# IOBoard.net
KiCad netlist of a schematic drawn in EAGLE
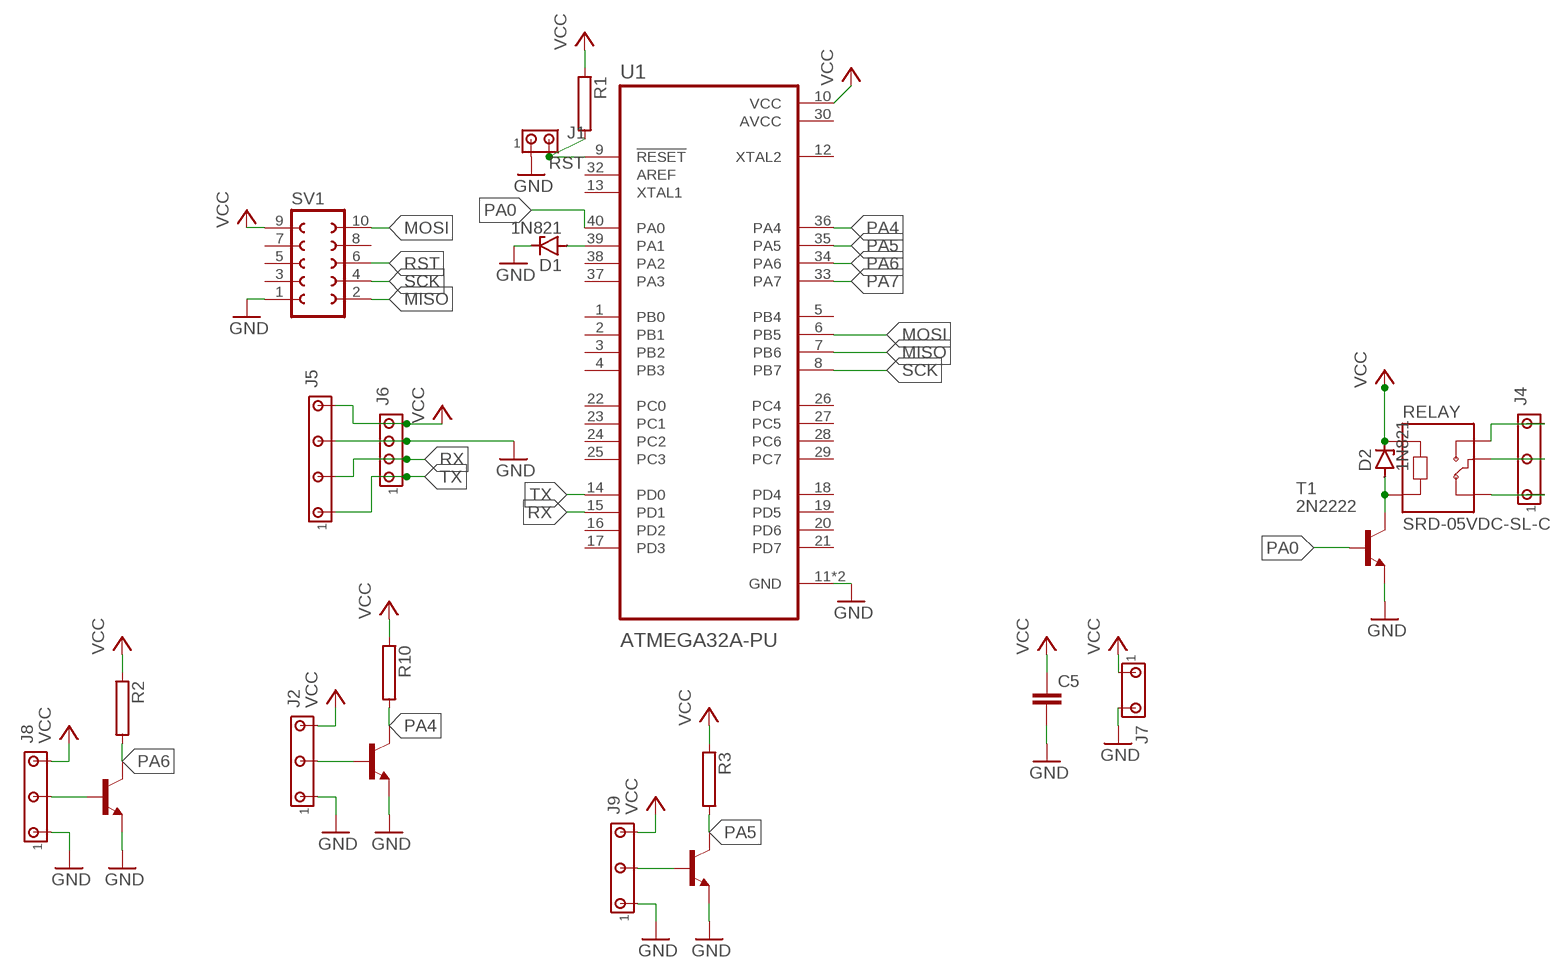
[diagram p0: schematic, sheet 1]

(export (version "E")
  (design (tool "Eeschema 10.0.6"))
  (components
    (comp (ref "C5")
      (value "C-EU025-024X044")
      (footprint "eagle-import:C025-024X044")
      (libsource (lib "eagle-import") (part "C-EU025-024X044"))
    )
    (comp (ref "D1")
      (value "1N821")
      (footprint "eagle-import:DO35Z10")
      (libsource (lib "eagle-import") (part "1N821"))
    )
    (comp (ref "D2")
      (value "1N821")
      (footprint "eagle-import:DO35Z10")
      (libsource (lib "eagle-import") (part "1N821"))
    )
    (comp (ref "J1")
      (value "MTA02-100")
      (footprint "eagle-import:10X02MTA")
      (libsource (lib "eagle-import") (part "MTA02-100"))
    )
    (comp (ref "J2")
      (value "MTA05-156_MYVSPACE1")
      (footprint "eagle-import:10X05MTA_MYV")
      (libsource (lib "eagle-import") (part "MTA05-156_MYVSPACE1"))
    )
    (comp (ref "J4")
      (value "MTA05-156_MYVSPACE1")
      (footprint "eagle-import:10X05MTA_MYV")
      (libsource (lib "eagle-import") (part "MTA05-156_MYVSPACE1"))
    )
    (comp (ref "J5")
      (value "MTA07-100_MYV")
      (footprint "eagle-import:10X07MTA_MYV")
      (libsource (lib "eagle-import") (part "MTA07-100_MYV"))
    )
    (comp (ref "J6")
      (value "MTA04-100")
      (footprint "eagle-import:10X04MTA")
      (libsource (lib "eagle-import") (part "MTA04-100"))
    )
    (comp (ref "J7")
      (value "MTA03-100_MYV")
      (footprint "eagle-import:10X03MTA_MYV")
      (libsource (lib "eagle-import") (part "MTA03-100_MYV"))
    )
    (comp (ref "J8")
      (value "MTA05-156_MYVSPACE1")
      (footprint "eagle-import:10X05MTA_MYV")
      (libsource (lib "eagle-import") (part "MTA05-156_MYVSPACE1"))
    )
    (comp (ref "J9")
      (value "MTA05-156_MYVSPACE1")
      (footprint "eagle-import:10X05MTA_MYV")
      (libsource (lib "eagle-import") (part "MTA05-156_MYVSPACE1"))
    )
    (comp (ref "R1")
      (value "RHPS58")
      (footprint "eagle-import:HPS58")
      (libsource (lib "eagle-import") (part "RHPS58"))
    )
    (comp (ref "R2")
      (value "RHPS58")
      (footprint "eagle-import:HPS58")
      (libsource (lib "eagle-import") (part "RHPS58"))
    )
    (comp (ref "R3")
      (value "RHPS58")
      (footprint "eagle-import:HPS58")
      (libsource (lib "eagle-import") (part "RHPS58"))
    )
    (comp (ref "R10")
      (value "RHPS58")
      (footprint "eagle-import:HPS58")
      (libsource (lib "eagle-import") (part "RHPS58"))
    )
    (comp (ref "RELAY")
      (value "SRD-05VDC-SL-C")
      (footprint "eagle-import:RELAY_SRD-05VDC-SL-C")
      (fields (field (name "MF") "Songle Relay"))
      (libsource (lib "eagle-import") (part "SRD-05VDC-SL-C"))
    )
    (comp (ref "SV1")
      (value "FE05-2_MYV")
      (footprint "eagle-import:FE05-2")
      (libsource (lib "eagle-import") (part "FE05-2_MYV"))
    )
    (comp (ref "T1")
      (value "2N2222")
      (footprint "eagle-import:TO18")
      (libsource (lib "eagle-import") (part "2N2222"))
    )
    (comp (ref "T2")
      (value "2N2222")
      (footprint "eagle-import:TO18")
      (libsource (lib "eagle-import") (part "2N2222"))
    )
    (comp (ref "T5")
      (value "2N2222")
      (footprint "eagle-import:TO18")
      (libsource (lib "eagle-import") (part "2N2222"))
    )
    (comp (ref "T6")
      (value "2N2222")
      (footprint "eagle-import:TO18")
      (libsource (lib "eagle-import") (part "2N2222"))
    )
    (comp (ref "U1")
      (value "ATMEGA32A-PU")
      (footprint "eagle-import:DIP1540W47P254L5320H635Q40B")
      (fields (field (name "MF") "Microchip Technology"))
      (libsource (lib "eagle-import") (part "ATMEGA32A-PU"))
    )
  )
  (nets
    (net (code "1") (name "/AVCC") (class "Default")
      (node (ref "U1") (pin "30") (pinfunction "AVCC_30") (pintype "power_in"))
    )
    (net (code "2") (name "GND") (class "Default")
      (node (ref "C5") (pin "2") (pinfunction "2_2") (pintype "passive"))
      (node (ref "D1") (pin "C") (pinfunction "C_C") (pintype "passive"))
      (node (ref "J1") (pin "1") (pinfunction "1_1") (pintype "passive"))
      (node (ref "J2") (pin "1") (pinfunction "1_1") (pintype "passive"))
      (node (ref "J5") (pin "5") (pinfunction "5_5") (pintype "passive"))
      (node (ref "J6") (pin "3") (pinfunction "3_3") (pintype "passive"))
      (node (ref "J7") (pin "3") (pinfunction "3_3") (pintype "passive"))
      (node (ref "J8") (pin "1") (pinfunction "1_1") (pintype "passive"))
      (node (ref "J9") (pin "1") (pinfunction "1_1") (pintype "passive"))
      (node (ref "SV1") (pin "1") (pinfunction "1_1") (pintype "passive"))
      (node (ref "T1") (pin "1") (pinfunction "E_1") (pintype "passive"))
      (node (ref "T2") (pin "1") (pinfunction "E_1") (pintype "passive"))
      (node (ref "T5") (pin "1") (pinfunction "E_1") (pintype "passive"))
      (node (ref "T6") (pin "1") (pinfunction "E_1") (pintype "passive"))
      (node (ref "U1") (pin "11") (pinfunction "GND_11") (pintype "power_in"))
      (node (ref "U1") (pin "31") (pinfunction "GND_31") (pintype "power_in"))
    )
    (net (code "3") (name "MISO") (class "Default")
      (node (ref "SV1") (pin "2") (pinfunction "2_2") (pintype "passive"))
      (node (ref "U1") (pin "7") (pinfunction "PB6_7") (pintype "bidirectional"))
    )
    (net (code "4") (name "MOSI") (class "Default")
      (node (ref "SV1") (pin "10") (pinfunction "10_10") (pintype "passive"))
      (node (ref "U1") (pin "6") (pinfunction "PB5_6") (pintype "bidirectional"))
    )
    (net (code "5") (name "Net-(J4-Pad1)") (class "Default")
      (node (ref "J4") (pin "1") (pinfunction "1_1") (pintype "passive"))
      (node (ref "RELAY") (pin "NC") (pinfunction "NC_NC") (pintype "passive"))
    )
    (net (code "6") (name "Net-(J4-Pad3)") (class "Default")
      (node (ref "J4") (pin "3") (pinfunction "3_3") (pintype "passive"))
      (node (ref "RELAY") (pin "COM") (pinfunction "COM_COM") (pintype "passive"))
    )
    (net (code "7") (name "Net-(J4-Pad5)") (class "Default")
      (node (ref "J4") (pin "5") (pinfunction "5_5") (pintype "passive"))
      (node (ref "RELAY") (pin "NO") (pinfunction "NO_NO") (pintype "passive"))
    )
    (net (code "8") (name "Net-(T1-C)") (class "Default")
      (node (ref "D2") (pin "A") (pinfunction "A_A") (pintype "passive"))
      (node (ref "RELAY") (pin "A2") (pinfunction "A2_A2") (pintype "passive"))
      (node (ref "T1") (pin "3") (pinfunction "C_3") (pintype "passive"))
    )
    (net (code "9") (name "Net-(T2-B)") (class "Default")
      (node (ref "J2") (pin "3") (pinfunction "3_3") (pintype "passive"))
      (node (ref "T2") (pin "2") (pinfunction "B_2") (pintype "passive"))
    )
    (net (code "10") (name "Net-(T5-B)") (class "Default")
      (node (ref "J8") (pin "3") (pinfunction "3_3") (pintype "passive"))
      (node (ref "T5") (pin "2") (pinfunction "B_2") (pintype "passive"))
    )
    (net (code "11") (name "Net-(T6-B)") (class "Default")
      (node (ref "J9") (pin "3") (pinfunction "3_3") (pintype "passive"))
      (node (ref "T6") (pin "2") (pinfunction "B_2") (pintype "passive"))
    )
    (net (code "12") (name "Net-(U1-PA1)") (class "Default")
      (node (ref "D1") (pin "A") (pinfunction "A_A") (pintype "passive"))
      (node (ref "U1") (pin "39") (pinfunction "PA1_39") (pintype "bidirectional"))
    )
    (net (code "13") (name "PA0") (class "Default")
      (node (ref "T1") (pin "2") (pinfunction "B_2") (pintype "passive"))
      (node (ref "U1") (pin "40") (pinfunction "PA0_40") (pintype "bidirectional"))
    )
    (net (code "14") (name "PA4") (class "Default")
      (node (ref "R10") (pin "2") (pinfunction "2_2") (pintype "passive"))
      (node (ref "T2") (pin "3") (pinfunction "C_3") (pintype "passive"))
      (node (ref "U1") (pin "36") (pinfunction "PA4_36") (pintype "bidirectional"))
    )
    (net (code "15") (name "PA5") (class "Default")
      (node (ref "R3") (pin "2") (pinfunction "2_2") (pintype "passive"))
      (node (ref "T6") (pin "3") (pinfunction "C_3") (pintype "passive"))
      (node (ref "U1") (pin "35") (pinfunction "PA5_35") (pintype "bidirectional"))
    )
    (net (code "16") (name "PA6") (class "Default")
      (node (ref "R2") (pin "2") (pinfunction "2_2") (pintype "passive"))
      (node (ref "T5") (pin "3") (pinfunction "C_3") (pintype "passive"))
      (node (ref "U1") (pin "34") (pinfunction "PA6_34") (pintype "bidirectional"))
    )
    (net (code "17") (name "PA7") (class "Default")
      (node (ref "U1") (pin "33") (pinfunction "PA7_33") (pintype "bidirectional"))
    )
    (net (code "18") (name "RST") (class "Default")
      (node (ref "J1") (pin "2") (pinfunction "2_2") (pintype "passive"))
      (node (ref "R1") (pin "2") (pinfunction "2_2") (pintype "passive"))
      (node (ref "SV1") (pin "6") (pinfunction "6_6") (pintype "passive"))
      (node (ref "U1") (pin "9") (pinfunction "~{RESET}_9") (pintype "input"))
    )
    (net (code "19") (name "RX") (class "Default")
      (node (ref "J5") (pin "3") (pinfunction "3_3") (pintype "passive"))
      (node (ref "J6") (pin "2") (pinfunction "2_2") (pintype "passive"))
      (node (ref "U1") (pin "15") (pinfunction "PD1_15") (pintype "bidirectional"))
    )
    (net (code "20") (name "SCK") (class "Default")
      (node (ref "SV1") (pin "4") (pinfunction "4_4") (pintype "passive"))
      (node (ref "U1") (pin "8") (pinfunction "PB7_8") (pintype "bidirectional"))
    )
    (net (code "21") (name "TX") (class "Default")
      (node (ref "J5") (pin "1") (pinfunction "1_1") (pintype "passive"))
      (node (ref "J6") (pin "1") (pinfunction "1_1") (pintype "passive"))
      (node (ref "U1") (pin "14") (pinfunction "PD0_14") (pintype "bidirectional"))
    )
    (net (code "22") (name "VCC") (class "Default")
      (node (ref "C5") (pin "1") (pinfunction "1_1") (pintype "passive"))
      (node (ref "D2") (pin "C") (pinfunction "C_C") (pintype "passive"))
      (node (ref "J2") (pin "5") (pinfunction "5_5") (pintype "passive"))
      (node (ref "J5") (pin "7") (pinfunction "7_7") (pintype "passive"))
      (node (ref "J6") (pin "4") (pinfunction "4_4") (pintype "passive"))
      (node (ref "J7") (pin "1") (pinfunction "1_1") (pintype "passive"))
      (node (ref "J8") (pin "5") (pinfunction "5_5") (pintype "passive"))
      (node (ref "J9") (pin "5") (pinfunction "5_5") (pintype "passive"))
      (node (ref "R1") (pin "1") (pinfunction "1_1") (pintype "passive"))
      (node (ref "R10") (pin "1") (pinfunction "1_1") (pintype "passive"))
      (node (ref "R2") (pin "1") (pinfunction "1_1") (pintype "passive"))
      (node (ref "R3") (pin "1") (pinfunction "1_1") (pintype "passive"))
      (node (ref "RELAY") (pin "A1") (pinfunction "A1_A1") (pintype "passive"))
      (node (ref "SV1") (pin "9") (pinfunction "9_9") (pintype "passive"))
      (node (ref "U1") (pin "10") (pinfunction "VCC_10") (pintype "power_in"))
    )
    (net (code "23") (name "unconnected-(SV1-Pad3)") (class "Default")
      (node (ref "SV1") (pin "3") (pinfunction "3_3") (pintype "passive"))
    )
    (net (code "24") (name "unconnected-(SV1-Pad5)") (class "Default")
      (node (ref "SV1") (pin "5") (pinfunction "5_5") (pintype "passive"))
    )
    (net (code "25") (name "unconnected-(SV1-Pad7)") (class "Default")
      (node (ref "SV1") (pin "7") (pinfunction "7_7") (pintype "passive"))
    )
    (net (code "26") (name "unconnected-(SV1-Pad8)") (class "Default")
      (node (ref "SV1") (pin "8") (pinfunction "8_8") (pintype "passive"))
    )
    (net (code "27") (name "unconnected-(U1-AREF-Pad32)") (class "Default")
      (node (ref "U1") (pin "32") (pinfunction "AREF_32") (pintype "input"))
    )
    (net (code "28") (name "unconnected-(U1-PA2-Pad38)") (class "Default")
      (node (ref "U1") (pin "38") (pinfunction "PA2_38") (pintype "bidirectional"))
    )
    (net (code "29") (name "unconnected-(U1-PA3-Pad37)") (class "Default")
      (node (ref "U1") (pin "37") (pinfunction "PA3_37") (pintype "bidirectional"))
    )
    (net (code "30") (name "unconnected-(U1-PB0-Pad1)") (class "Default")
      (node (ref "U1") (pin "1") (pinfunction "PB0_1") (pintype "bidirectional"))
    )
    (net (code "31") (name "unconnected-(U1-PB1-Pad2)") (class "Default")
      (node (ref "U1") (pin "2") (pinfunction "PB1_2") (pintype "bidirectional"))
    )
    (net (code "32") (name "unconnected-(U1-PB2-Pad3)") (class "Default")
      (node (ref "U1") (pin "3") (pinfunction "PB2_3") (pintype "bidirectional"))
    )
    (net (code "33") (name "unconnected-(U1-PB3-Pad4)") (class "Default")
      (node (ref "U1") (pin "4") (pinfunction "PB3_4") (pintype "bidirectional"))
    )
    (net (code "34") (name "unconnected-(U1-PB4-Pad5)") (class "Default")
      (node (ref "U1") (pin "5") (pinfunction "PB4_5") (pintype "bidirectional"))
    )
    (net (code "35") (name "unconnected-(U1-PC0-Pad22)") (class "Default")
      (node (ref "U1") (pin "22") (pinfunction "PC0_22") (pintype "bidirectional"))
    )
    (net (code "36") (name "unconnected-(U1-PC1-Pad23)") (class "Default")
      (node (ref "U1") (pin "23") (pinfunction "PC1_23") (pintype "bidirectional"))
    )
    (net (code "37") (name "unconnected-(U1-PC2-Pad24)") (class "Default")
      (node (ref "U1") (pin "24") (pinfunction "PC2_24") (pintype "bidirectional"))
    )
    (net (code "38") (name "unconnected-(U1-PC3-Pad25)") (class "Default")
      (node (ref "U1") (pin "25") (pinfunction "PC3_25") (pintype "bidirectional"))
    )
    (net (code "39") (name "unconnected-(U1-PC4-Pad26)") (class "Default")
      (node (ref "U1") (pin "26") (pinfunction "PC4_26") (pintype "bidirectional"))
    )
    (net (code "40") (name "unconnected-(U1-PC5-Pad27)") (class "Default")
      (node (ref "U1") (pin "27") (pinfunction "PC5_27") (pintype "bidirectional"))
    )
    (net (code "41") (name "unconnected-(U1-PC6-Pad28)") (class "Default")
      (node (ref "U1") (pin "28") (pinfunction "PC6_28") (pintype "bidirectional"))
    )
    (net (code "42") (name "unconnected-(U1-PC7-Pad29)") (class "Default")
      (node (ref "U1") (pin "29") (pinfunction "PC7_29") (pintype "bidirectional"))
    )
    (net (code "43") (name "unconnected-(U1-PD2-Pad16)") (class "Default")
      (node (ref "U1") (pin "16") (pinfunction "PD2_16") (pintype "bidirectional"))
    )
    (net (code "44") (name "unconnected-(U1-PD3-Pad17)") (class "Default")
      (node (ref "U1") (pin "17") (pinfunction "PD3_17") (pintype "bidirectional"))
    )
    (net (code "45") (name "unconnected-(U1-PD4-Pad18)") (class "Default")
      (node (ref "U1") (pin "18") (pinfunction "PD4_18") (pintype "bidirectional"))
    )
    (net (code "46") (name "unconnected-(U1-PD5-Pad19)") (class "Default")
      (node (ref "U1") (pin "19") (pinfunction "PD5_19") (pintype "bidirectional"))
    )
    (net (code "47") (name "unconnected-(U1-PD6-Pad20)") (class "Default")
      (node (ref "U1") (pin "20") (pinfunction "PD6_20") (pintype "bidirectional"))
    )
    (net (code "48") (name "unconnected-(U1-PD7-Pad21)") (class "Default")
      (node (ref "U1") (pin "21") (pinfunction "PD7_21") (pintype "bidirectional"))
    )
    (net (code "49") (name "unconnected-(U1-XTAL1-Pad13)") (class "Default")
      (node (ref "U1") (pin "13") (pinfunction "XTAL1_13") (pintype "input"))
    )
    (net (code "50") (name "unconnected-(U1-XTAL2-Pad12)") (class "Default")
      (node (ref "U1") (pin "12") (pinfunction "XTAL2_12") (pintype "output"))
    )
  )
)
